# 8_Channel_Current_Sensor.net
KiCad netlist of a schematic drawn in EAGLE
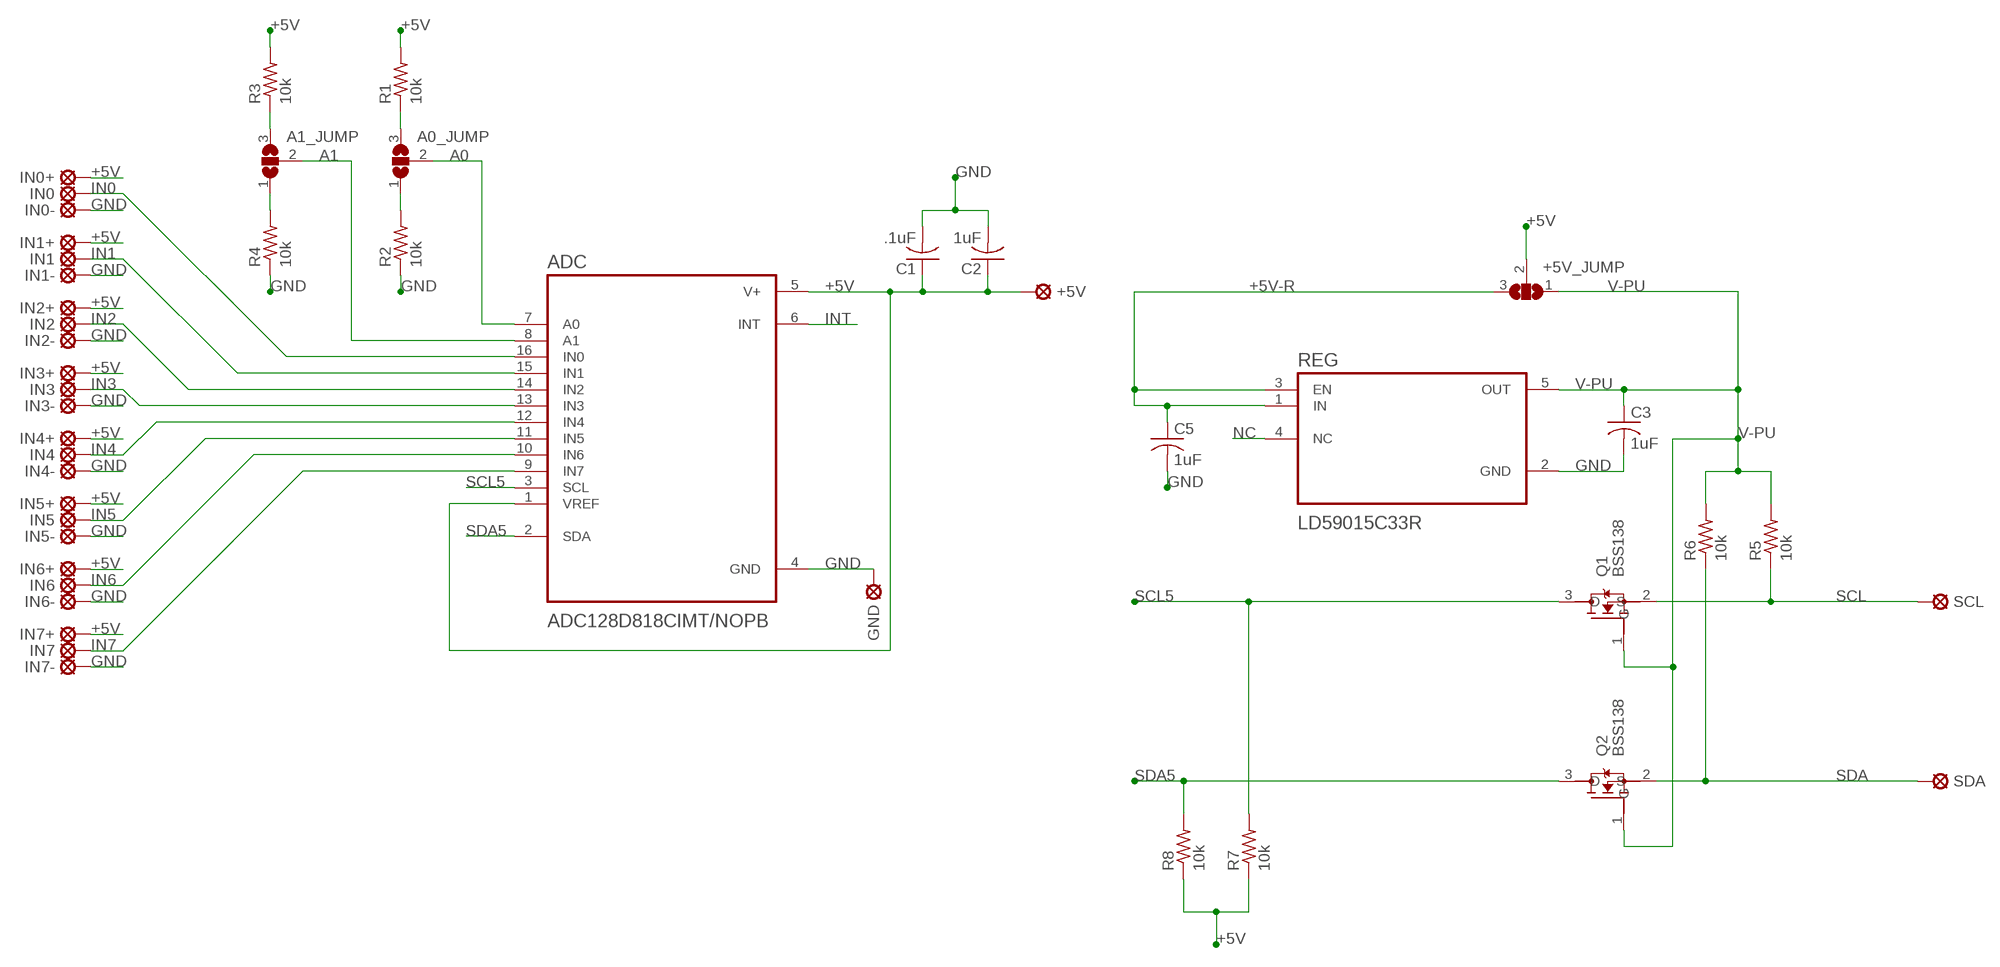
[diagram p0: schematic, sheet 1]

(export (version "E")
  (design (tool "Eeschema 10.0.6"))
  (components
    (comp (ref "+5V")
      (value "LSP10")
      (footprint "eagle-import:LSP10")
      (libsource (lib "eagle-import") (part "LSP10"))
    )
    (comp (ref "+5V_JUMP")
      (value "SJ2W")
      (footprint "eagle-import:SJ_2")
      (libsource (lib "eagle-import") (part "SJ2W"))
    )
    (comp (ref "A0_JUMP")
      (value "SJ2W")
      (footprint "eagle-import:SJ_2")
      (libsource (lib "eagle-import") (part "SJ2W"))
    )
    (comp (ref "A1_JUMP")
      (value "SJ2W")
      (footprint "eagle-import:SJ_2")
      (libsource (lib "eagle-import") (part "SJ2W"))
    )
    (comp (ref "ADC")
      (value "ADC128D818CIMT/NOPB")
      (footprint "eagle-import:SOP65P640X120-16N")
      (fields (field (name "MF") "Texas Instruments"))
      (libsource (lib "eagle-import") (part "ADC128D818CIMT/NOPB"))
    )
    (comp (ref "C1")
      (value ".1uF")
      (footprint "eagle-import:C0603")
      (libsource (lib "eagle-import") (part "C-USC0603"))
    )
    (comp (ref "C2")
      (value "1uF")
      (footprint "eagle-import:C0603")
      (libsource (lib "eagle-import") (part "C-USC0603"))
    )
    (comp (ref "C3")
      (value "1uF")
      (footprint "eagle-import:C0603")
      (libsource (lib "eagle-import") (part "C-USC0603"))
    )
    (comp (ref "C5")
      (value "1uF")
      (footprint "eagle-import:C0603")
      (libsource (lib "eagle-import") (part "C-USC0603"))
    )
    (comp (ref "GND")
      (value "LSP10")
      (footprint "eagle-import:LSP10")
      (libsource (lib "eagle-import") (part "LSP10"))
    )
    (comp (ref "IN0")
      (value "LSP10")
      (footprint "eagle-import:LSP10")
      (libsource (lib "eagle-import") (part "LSP10"))
    )
    (comp (ref "IN0+")
      (value "LSP10")
      (footprint "eagle-import:LSP10")
      (libsource (lib "eagle-import") (part "LSP10"))
    )
    (comp (ref "IN0-")
      (value "LSP10")
      (footprint "eagle-import:LSP10")
      (libsource (lib "eagle-import") (part "LSP10"))
    )
    (comp (ref "IN1")
      (value "LSP10")
      (footprint "eagle-import:LSP10")
      (libsource (lib "eagle-import") (part "LSP10"))
    )
    (comp (ref "IN1+")
      (value "LSP10")
      (footprint "eagle-import:LSP10")
      (libsource (lib "eagle-import") (part "LSP10"))
    )
    (comp (ref "IN1-")
      (value "LSP10")
      (footprint "eagle-import:LSP10")
      (libsource (lib "eagle-import") (part "LSP10"))
    )
    (comp (ref "IN2")
      (value "LSP10")
      (footprint "eagle-import:LSP10")
      (libsource (lib "eagle-import") (part "LSP10"))
    )
    (comp (ref "IN2+")
      (value "LSP10")
      (footprint "eagle-import:LSP10")
      (libsource (lib "eagle-import") (part "LSP10"))
    )
    (comp (ref "IN2-")
      (value "LSP10")
      (footprint "eagle-import:LSP10")
      (libsource (lib "eagle-import") (part "LSP10"))
    )
    (comp (ref "IN3")
      (value "LSP10")
      (footprint "eagle-import:LSP10")
      (libsource (lib "eagle-import") (part "LSP10"))
    )
    (comp (ref "IN3+")
      (value "LSP10")
      (footprint "eagle-import:LSP10")
      (libsource (lib "eagle-import") (part "LSP10"))
    )
    (comp (ref "IN3-")
      (value "LSP10")
      (footprint "eagle-import:LSP10")
      (libsource (lib "eagle-import") (part "LSP10"))
    )
    (comp (ref "IN4")
      (value "LSP10")
      (footprint "eagle-import:LSP10")
      (libsource (lib "eagle-import") (part "LSP10"))
    )
    (comp (ref "IN4+")
      (value "LSP10")
      (footprint "eagle-import:LSP10")
      (libsource (lib "eagle-import") (part "LSP10"))
    )
    (comp (ref "IN4-")
      (value "LSP10")
      (footprint "eagle-import:LSP10")
      (libsource (lib "eagle-import") (part "LSP10"))
    )
    (comp (ref "IN5")
      (value "LSP10")
      (footprint "eagle-import:LSP10")
      (libsource (lib "eagle-import") (part "LSP10"))
    )
    (comp (ref "IN5+")
      (value "LSP10")
      (footprint "eagle-import:LSP10")
      (libsource (lib "eagle-import") (part "LSP10"))
    )
    (comp (ref "IN5-")
      (value "LSP10")
      (footprint "eagle-import:LSP10")
      (libsource (lib "eagle-import") (part "LSP10"))
    )
    (comp (ref "IN6")
      (value "LSP10")
      (footprint "eagle-import:LSP10")
      (libsource (lib "eagle-import") (part "LSP10"))
    )
    (comp (ref "IN6+")
      (value "LSP10")
      (footprint "eagle-import:LSP10")
      (libsource (lib "eagle-import") (part "LSP10"))
    )
    (comp (ref "IN6-")
      (value "LSP10")
      (footprint "eagle-import:LSP10")
      (libsource (lib "eagle-import") (part "LSP10"))
    )
    (comp (ref "IN7")
      (value "LSP10")
      (footprint "eagle-import:LSP10")
      (libsource (lib "eagle-import") (part "LSP10"))
    )
    (comp (ref "IN7+")
      (value "LSP10")
      (footprint "eagle-import:LSP10")
      (libsource (lib "eagle-import") (part "LSP10"))
    )
    (comp (ref "IN7-")
      (value "LSP10")
      (footprint "eagle-import:LSP10")
      (libsource (lib "eagle-import") (part "LSP10"))
    )
    (comp (ref "Q1")
      (value "BSS138")
      (footprint "eagle-import:SOT95P240X120-3N")
      (fields (field (name "MF") "ON Semiconductor"))
      (libsource (lib "eagle-import") (part "BSS138"))
    )
    (comp (ref "Q2")
      (value "BSS138")
      (footprint "eagle-import:SOT95P240X120-3N")
      (fields (field (name "MF") "ON Semiconductor"))
      (libsource (lib "eagle-import") (part "BSS138"))
    )
    (comp (ref "R1")
      (value "10k")
      (footprint "eagle-import:R0603")
      (libsource (lib "eagle-import") (part "R-US_R0603"))
    )
    (comp (ref "R2")
      (value "10k")
      (footprint "eagle-import:R0603")
      (libsource (lib "eagle-import") (part "R-US_R0603"))
    )
    (comp (ref "R3")
      (value "10k")
      (footprint "eagle-import:R0603")
      (libsource (lib "eagle-import") (part "R-US_R0603"))
    )
    (comp (ref "R4")
      (value "10k")
      (footprint "eagle-import:R0603")
      (libsource (lib "eagle-import") (part "R-US_R0603"))
    )
    (comp (ref "R5")
      (value "10k")
      (footprint "eagle-import:R0603")
      (libsource (lib "eagle-import") (part "R-US_R0603"))
    )
    (comp (ref "R6")
      (value "10k")
      (footprint "eagle-import:R0603")
      (libsource (lib "eagle-import") (part "R-US_R0603"))
    )
    (comp (ref "R7")
      (value "10k")
      (footprint "eagle-import:R0603")
      (libsource (lib "eagle-import") (part "R-US_R0603"))
    )
    (comp (ref "R8")
      (value "10k")
      (footprint "eagle-import:R0603")
      (libsource (lib "eagle-import") (part "R-US_R0603"))
    )
    (comp (ref "REG")
      (value "LD59015C33R")
      (footprint "eagle-import:SOT65P210X110-5N")
      (fields (field (name "MF") "STMicroelectronics"))
      (libsource (lib "eagle-import") (part "LD59015C33R"))
    )
    (comp (ref "SCL")
      (value "LSP10")
      (footprint "eagle-import:LSP10")
      (libsource (lib "eagle-import") (part "LSP10"))
    )
    (comp (ref "SDA")
      (value "LSP10")
      (footprint "eagle-import:LSP10")
      (libsource (lib "eagle-import") (part "LSP10"))
    )
  )
  (nets
    (net (code "1") (name "/+5V") (class "Default")
      (node (ref "+5V") (pin "MP") (pinfunction "MP_MP") (pintype "passive"))
      (node (ref "+5V_JUMP") (pin "2") (pinfunction "2_2") (pintype "passive"))
      (node (ref "ADC") (pin "1") (pinfunction "VREF_1") (pintype "input"))
      (node (ref "ADC") (pin "5") (pinfunction "V+_5") (pintype "power_in"))
      (node (ref "C1") (pin "1") (pinfunction "1_1") (pintype "passive"))
      (node (ref "C2") (pin "1") (pinfunction "1_1") (pintype "passive"))
      (node (ref "IN0+") (pin "MP") (pinfunction "MP_MP") (pintype "passive"))
      (node (ref "IN1+") (pin "MP") (pinfunction "MP_MP") (pintype "passive"))
      (node (ref "IN2+") (pin "MP") (pinfunction "MP_MP") (pintype "passive"))
      (node (ref "IN3+") (pin "MP") (pinfunction "MP_MP") (pintype "passive"))
      (node (ref "IN4+") (pin "MP") (pinfunction "MP_MP") (pintype "passive"))
      (node (ref "IN5+") (pin "MP") (pinfunction "MP_MP") (pintype "passive"))
      (node (ref "IN6+") (pin "MP") (pinfunction "MP_MP") (pintype "passive"))
      (node (ref "IN7+") (pin "MP") (pinfunction "MP_MP") (pintype "passive"))
      (node (ref "R1") (pin "2") (pinfunction "2_2") (pintype "passive"))
      (node (ref "R3") (pin "2") (pinfunction "2_2") (pintype "passive"))
      (node (ref "R7") (pin "1") (pinfunction "1_1") (pintype "passive"))
      (node (ref "R8") (pin "1") (pinfunction "1_1") (pintype "passive"))
    )
    (net (code "2") (name "/+5V-R") (class "Default")
      (node (ref "+5V_JUMP") (pin "3") (pinfunction "3_3") (pintype "passive"))
      (node (ref "C5") (pin "1") (pinfunction "1_1") (pintype "passive"))
      (node (ref "REG") (pin "1") (pinfunction "IN_1") (pintype "input"))
      (node (ref "REG") (pin "3") (pinfunction "EN_3") (pintype "input"))
    )
    (net (code "3") (name "/A0") (class "Default")
      (node (ref "A0_JUMP") (pin "2") (pinfunction "2_2") (pintype "passive"))
      (node (ref "ADC") (pin "7") (pinfunction "A0_7") (pintype "input"))
    )
    (net (code "4") (name "/A1") (class "Default")
      (node (ref "A1_JUMP") (pin "2") (pinfunction "2_2") (pintype "passive"))
      (node (ref "ADC") (pin "8") (pinfunction "A1_8") (pintype "input"))
    )
    (net (code "5") (name "/GND") (class "Default")
      (node (ref "ADC") (pin "4") (pinfunction "GND_4") (pintype "power_in"))
      (node (ref "C1") (pin "2") (pinfunction "2_2") (pintype "passive"))
      (node (ref "C2") (pin "2") (pinfunction "2_2") (pintype "passive"))
      (node (ref "C3") (pin "2") (pinfunction "2_2") (pintype "passive"))
      (node (ref "C5") (pin "2") (pinfunction "2_2") (pintype "passive"))
      (node (ref "GND") (pin "MP") (pinfunction "MP_MP") (pintype "passive"))
      (node (ref "IN0-") (pin "MP") (pinfunction "MP_MP") (pintype "passive"))
      (node (ref "IN1-") (pin "MP") (pinfunction "MP_MP") (pintype "passive"))
      (node (ref "IN2-") (pin "MP") (pinfunction "MP_MP") (pintype "passive"))
      (node (ref "IN3-") (pin "MP") (pinfunction "MP_MP") (pintype "passive"))
      (node (ref "IN4-") (pin "MP") (pinfunction "MP_MP") (pintype "passive"))
      (node (ref "IN5-") (pin "MP") (pinfunction "MP_MP") (pintype "passive"))
      (node (ref "IN6-") (pin "MP") (pinfunction "MP_MP") (pintype "passive"))
      (node (ref "IN7-") (pin "MP") (pinfunction "MP_MP") (pintype "passive"))
      (node (ref "R2") (pin "1") (pinfunction "1_1") (pintype "passive"))
      (node (ref "R4") (pin "1") (pinfunction "1_1") (pintype "passive"))
      (node (ref "REG") (pin "2") (pinfunction "GND_2") (pintype "power_in"))
    )
    (net (code "6") (name "/IN0") (class "Default")
      (node (ref "ADC") (pin "16") (pinfunction "IN0_16") (pintype "input"))
      (node (ref "IN0") (pin "MP") (pinfunction "MP_MP") (pintype "passive"))
    )
    (net (code "7") (name "/IN1") (class "Default")
      (node (ref "ADC") (pin "15") (pinfunction "IN1_15") (pintype "input"))
      (node (ref "IN1") (pin "MP") (pinfunction "MP_MP") (pintype "passive"))
    )
    (net (code "8") (name "/IN2") (class "Default")
      (node (ref "ADC") (pin "14") (pinfunction "IN2_14") (pintype "input"))
      (node (ref "IN2") (pin "MP") (pinfunction "MP_MP") (pintype "passive"))
    )
    (net (code "9") (name "/IN3") (class "Default")
      (node (ref "ADC") (pin "13") (pinfunction "IN3_13") (pintype "input"))
      (node (ref "IN3") (pin "MP") (pinfunction "MP_MP") (pintype "passive"))
    )
    (net (code "10") (name "/IN4") (class "Default")
      (node (ref "ADC") (pin "12") (pinfunction "IN4_12") (pintype "input"))
      (node (ref "IN4") (pin "MP") (pinfunction "MP_MP") (pintype "passive"))
    )
    (net (code "11") (name "/IN5") (class "Default")
      (node (ref "ADC") (pin "11") (pinfunction "IN5_11") (pintype "input"))
      (node (ref "IN5") (pin "MP") (pinfunction "MP_MP") (pintype "passive"))
    )
    (net (code "12") (name "/IN6") (class "Default")
      (node (ref "ADC") (pin "10") (pinfunction "IN6_10") (pintype "input"))
      (node (ref "IN6") (pin "MP") (pinfunction "MP_MP") (pintype "passive"))
    )
    (net (code "13") (name "/IN7") (class "Default")
      (node (ref "ADC") (pin "9") (pinfunction "IN7_9") (pintype "input"))
      (node (ref "IN7") (pin "MP") (pinfunction "MP_MP") (pintype "passive"))
    )
    (net (code "14") (name "/INT") (class "Default")
      (node (ref "ADC") (pin "6") (pinfunction "INT_6") (pintype "output"))
    )
    (net (code "15") (name "/NC") (class "Default")
      (node (ref "REG") (pin "4") (pinfunction "NC_4") (pintype "bidirectional"))
    )
    (net (code "16") (name "/SCL") (class "Default")
      (node (ref "Q1") (pin "2") (pinfunction "S_2") (pintype "passive"))
      (node (ref "R5") (pin "1") (pinfunction "1_1") (pintype "passive"))
      (node (ref "SCL") (pin "MP") (pinfunction "MP_MP") (pintype "passive"))
    )
    (net (code "17") (name "/SCL5") (class "Default")
      (node (ref "ADC") (pin "3") (pinfunction "SCL_3") (pintype "input"))
      (node (ref "Q1") (pin "3") (pinfunction "D_3") (pintype "passive"))
      (node (ref "R7") (pin "2") (pinfunction "2_2") (pintype "passive"))
    )
    (net (code "18") (name "/SDA") (class "Default")
      (node (ref "Q2") (pin "2") (pinfunction "S_2") (pintype "passive"))
      (node (ref "R6") (pin "1") (pinfunction "1_1") (pintype "passive"))
      (node (ref "SDA") (pin "MP") (pinfunction "MP_MP") (pintype "passive"))
    )
    (net (code "19") (name "/SDA5") (class "Default")
      (node (ref "ADC") (pin "2") (pinfunction "SDA_2") (pintype "bidirectional"))
      (node (ref "Q2") (pin "3") (pinfunction "D_3") (pintype "passive"))
      (node (ref "R8") (pin "2") (pinfunction "2_2") (pintype "passive"))
    )
    (net (code "20") (name "/V-PU") (class "Default")
      (node (ref "+5V_JUMP") (pin "1") (pinfunction "1_1") (pintype "passive"))
      (node (ref "C3") (pin "1") (pinfunction "1_1") (pintype "passive"))
      (node (ref "Q1") (pin "1") (pinfunction "G_1") (pintype "passive"))
      (node (ref "Q2") (pin "1") (pinfunction "G_1") (pintype "passive"))
      (node (ref "R5") (pin "2") (pinfunction "2_2") (pintype "passive"))
      (node (ref "R6") (pin "2") (pinfunction "2_2") (pintype "passive"))
      (node (ref "REG") (pin "5") (pinfunction "OUT_5") (pintype "output"))
    )
    (net (code "21") (name "Net-(A0_JUMP-Pad1)") (class "Default")
      (node (ref "A0_JUMP") (pin "1") (pinfunction "1_1") (pintype "passive"))
      (node (ref "R2") (pin "2") (pinfunction "2_2") (pintype "passive"))
    )
    (net (code "22") (name "Net-(A0_JUMP-Pad3)") (class "Default")
      (node (ref "A0_JUMP") (pin "3") (pinfunction "3_3") (pintype "passive"))
      (node (ref "R1") (pin "1") (pinfunction "1_1") (pintype "passive"))
    )
    (net (code "23") (name "Net-(A1_JUMP-Pad1)") (class "Default")
      (node (ref "A1_JUMP") (pin "1") (pinfunction "1_1") (pintype "passive"))
      (node (ref "R4") (pin "2") (pinfunction "2_2") (pintype "passive"))
    )
    (net (code "24") (name "Net-(A1_JUMP-Pad3)") (class "Default")
      (node (ref "A1_JUMP") (pin "3") (pinfunction "3_3") (pintype "passive"))
      (node (ref "R3") (pin "1") (pinfunction "1_1") (pintype "passive"))
    )
  )
)
